# MicroController_USB_to_UART_Converter.net
KiCad netlist of a schematic drawn in Altium Designer
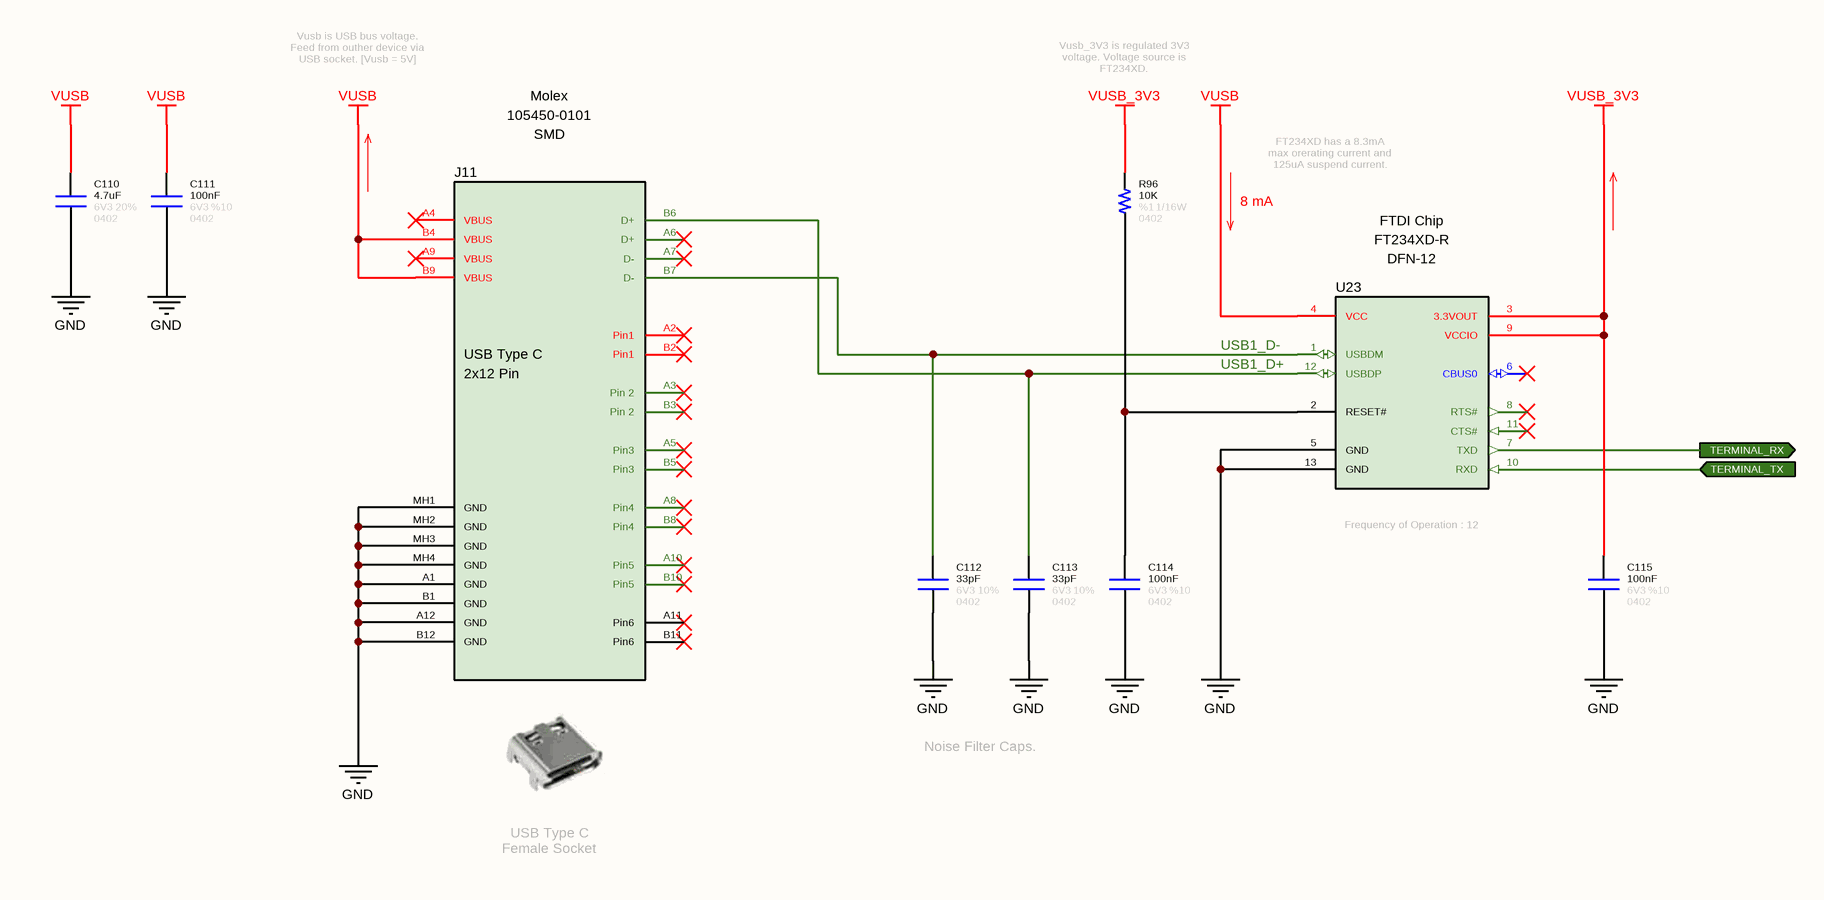
[diagram p0: MicroController USB to UART Converter.SchDoc]

(export (version "E")
  (design (tool "Eeschema 10.0.6"))
  (components
    (comp (ref "C110")
      (value "4.7uF")
      (footprint "CAPACITOR_0402")
      (description "Multilayer Ceramic Capacitors - SMD - 6V3 4.7uF X5R 0402 20%")
      (fields
        (field (name "MANUFACTURER PART NUMBER") "C0402C475M9PACTU")
        (field (name "TOLERANCE") "20%")
        (field (name "CASE") "0402")
        (field (name "VOLTAGE") "6V3")
        (field (name "Comment") "Capacitor - 4.7uF [0402] (Ceramic)")
      )
      (libsource (lib "Akkoyun") (part "Capacitor - 4.7uF [0402-6V3]"))
    )
    (comp (ref "C111")
      (value "100nF")
      (footprint "CAPACITOR_0402")
      (description "Capacitor - 100nF [0402-6V3] (Ceramic)")
      (fields
        (field (name "MANUFACTURER PART NUMBER") "04026D104KAT4A")
        (field (name "TOLERANCE") "%10")
        (field (name "VOLTAGE") "6V3")
        (field (name "CASE") "0402")
        (field (name "Comment") "Capacitor - 100nF [0402] (Ceramic)")
      )
      (libsource (lib "Akkoyun") (part "Capacitor - 100nF [0402-6V3]"))
    )
    (comp (ref "C112")
      (value "33pF")
      (footprint "CAPACITOR_0402")
      (description "Capacitor - 33pF [0402] (Ceramic)")
      (fields
        (field (name "MANUFACTURER PART NUMBER") "C0402C330J9RACAUTO")
        (field (name "TOLERANCE") "10%")
        (field (name "CASE") "0402")
        (field (name "VOLTAGE") "6V3")
      )
      (libsource (lib "Akkoyun") (part "Capacitor - 33pF [0402-6V3]"))
    )
    (comp (ref "C113")
      (value "33pF")
      (footprint "CAPACITOR_0402")
      (description "Capacitor - 33pF [0402] (Ceramic)")
      (fields
        (field (name "MANUFACTURER PART NUMBER") "C0402C330J9RACAUTO")
        (field (name "TOLERANCE") "10%")
        (field (name "CASE") "0402")
        (field (name "VOLTAGE") "6V3")
      )
      (libsource (lib "Akkoyun") (part "Capacitor - 33pF [0402-6V3]"))
    )
    (comp (ref "C114")
      (value "100nF")
      (footprint "CAPACITOR_0402")
      (description "Capacitor - 100nF [0402-6V3] (Ceramic)")
      (fields
        (field (name "MANUFACTURER PART NUMBER") "04026D104KAT4A")
        (field (name "TOLERANCE") "%10")
        (field (name "VOLTAGE") "6V3")
        (field (name "CASE") "0402")
        (field (name "Comment") "Capacitor - 100nF [0402] (Ceramic)")
      )
      (libsource (lib "Akkoyun") (part "Capacitor - 100nF [0402-6V3]"))
    )
    (comp (ref "C115")
      (value "100nF")
      (footprint "CAPACITOR_0402")
      (description "Capacitor - 100nF [0402-6V3] (Ceramic)")
      (fields
        (field (name "MANUFACTURER PART NUMBER") "04026D104KAT4A")
        (field (name "TOLERANCE") "%10")
        (field (name "VOLTAGE") "6V3")
        (field (name "CASE") "0402")
        (field (name "Comment") "Capacitor - 100nF [0402] (Ceramic)")
      )
      (libsource (lib "Akkoyun") (part "Capacitor - 100nF [0402-6V3]"))
    )
    (comp (ref "J11")
      (value "105450-0101")
      (footprint "USB Type C - Molex 105450-0101")
      (description "USB Shielded I/O Receptacle; Type C; Right Angle; Surface Mount; Gold over Nickel")
      (fields
        (field (name "MANUFACTURER NAME") "Molex")
        (field (name "MANUFACTURER PART NUMBER") "105450-0101")
        (field (name "CASE") "SMD")
      )
      (libsource (lib "Akkoyun") (part "Connector - USB Type C SMD Connector"))
    )
    (comp (ref "R96")
      (value "10K")
      (footprint "RESISTOR_0402")
      (description "Thick Film Resistors - SMD 1/16 W 10 KOhm 1%")
      (fields
        (field (name "MANUFACTURER PART NUMBER") "CRCW040210K0FKED")
        (field (name "TOLERANCE") "%1")
        (field (name "CASE") "0402")
        (field (name "POWER") "1/16W")
        (field (name "Comment") "10K - 0402 - %1 - 1/16W")
      )
      (libsource (lib "Akkoyun") (part "Resistor - 10K [0402]"))
    )
    (comp (ref "U23")
      (value "FT234XD-R")
      (footprint "FT234XD-R")
      (description "USB Interface IC USB to Serial UART Interface")
      (fields
        (field (name "MANUFACTURER NAME") "FTDI Chip")
        (field (name "MANUFACTURER PART NUMBER") "FT234XD-R")
        (field (name "CASE") "DFN-12")
      )
      (libsource (lib "Akkoyun") (part "IC - FT234XD-R"))
    )
  )
  (nets
    (net (code "1") (name "/TERMINAL_RX") (class "Default")
      (node (ref "U23") (pin "7") (pinfunction "TXD_7") (pintype "output"))
    )
    (net (code "2") (name "/TERMINAL_TX") (class "Default")
      (node (ref "U23") (pin "10") (pinfunction "RXD_10") (pintype "input"))
    )
    (net (code "3") (name "/USB1_D+") (class "Default")
      (node (ref "C113") (pin "2") (pinfunction "2_2") (pintype "passive"))
      (node (ref "J11") (pin "B6") (pinfunction "D+_B6") (pintype "passive"))
      (node (ref "U23") (pin "12") (pinfunction "USBDP_12") (pintype "bidirectional"))
    )
    (net (code "4") (name "/USB1_D-") (class "Default")
      (node (ref "C112") (pin "2") (pinfunction "2_2") (pintype "passive"))
      (node (ref "J11") (pin "B7") (pinfunction "D-_B7") (pintype "passive"))
      (node (ref "U23") (pin "1") (pinfunction "USBDM_1") (pintype "bidirectional"))
    )
    (net (code "5") (name "GND") (class "Default")
      (node (ref "C110") (pin "1") (pinfunction "1_1") (pintype "passive"))
      (node (ref "C111") (pin "1") (pinfunction "1_1") (pintype "passive"))
      (node (ref "C112") (pin "1") (pinfunction "1_1") (pintype "passive"))
      (node (ref "C113") (pin "1") (pinfunction "1_1") (pintype "passive"))
      (node (ref "C114") (pin "1") (pinfunction "1_1") (pintype "passive"))
      (node (ref "C115") (pin "1") (pinfunction "1_1") (pintype "passive"))
      (node (ref "J11") (pin "A1") (pinfunction "GND_A1") (pintype "passive"))
      (node (ref "J11") (pin "A12") (pinfunction "GND_A12") (pintype "passive"))
      (node (ref "J11") (pin "B1") (pinfunction "GND_B1") (pintype "passive"))
      (node (ref "J11") (pin "B12") (pinfunction "GND_B12") (pintype "passive"))
      (node (ref "J11") (pin "MH1") (pinfunction "GND_MH1") (pintype "passive"))
      (node (ref "J11") (pin "MH2") (pinfunction "GND_MH2") (pintype "passive"))
      (node (ref "J11") (pin "MH3") (pinfunction "GND_MH3") (pintype "passive"))
      (node (ref "J11") (pin "MH4") (pinfunction "GND_MH4") (pintype "passive"))
      (node (ref "U23") (pin "13") (pinfunction "GND_13") (pintype "power_in"))
      (node (ref "U23") (pin "5") (pinfunction "GND_5") (pintype "power_in"))
    )
    (net (code "6") (name "Net-(U23-RESET#)") (class "Default")
      (node (ref "C114") (pin "2") (pinfunction "2_2") (pintype "passive"))
      (node (ref "R96") (pin "1") (pinfunction "1_1") (pintype "passive"))
      (node (ref "U23") (pin "2") (pinfunction "RESET#_2") (pintype "passive"))
    )
    (net (code "7") (name "VUSB") (class "Default")
      (node (ref "C110") (pin "2") (pinfunction "2_2") (pintype "passive"))
      (node (ref "C111") (pin "2") (pinfunction "2_2") (pintype "passive"))
      (node (ref "J11") (pin "B4") (pinfunction "VBUS_B4") (pintype "passive"))
      (node (ref "J11") (pin "B9") (pinfunction "VBUS_B9") (pintype "passive"))
      (node (ref "U23") (pin "4") (pinfunction "VCC_4") (pintype "power_in"))
    )
    (net (code "8") (name "VUSB_3V3") (class "Default")
      (node (ref "C115") (pin "2") (pinfunction "2_2") (pintype "passive"))
      (node (ref "R96") (pin "2") (pinfunction "2_2") (pintype "passive"))
      (node (ref "U23") (pin "3") (pinfunction "3.3VOUT_3") (pintype "power_in"))
      (node (ref "U23") (pin "9") (pinfunction "VCCIO_9") (pintype "power_in"))
    )
    (net (code "9") (name "unconnected-(J11-D+-PadA6)") (class "Default")
      (node (ref "J11") (pin "A6") (pinfunction "D+_A6") (pintype "passive+no_connect"))
    )
    (net (code "10") (name "unconnected-(J11-D--PadA7)") (class "Default")
      (node (ref "J11") (pin "A7") (pinfunction "D-_A7") (pintype "passive+no_connect"))
    )
    (net (code "11") (name "unconnected-(J11-Pin1-PadA2)") (class "Default")
      (node (ref "J11") (pin "A2") (pinfunction "Pin1_A2") (pintype "passive+no_connect"))
    )
    (net (code "12") (name "unconnected-(J11-Pin1-PadB2)") (class "Default")
      (node (ref "J11") (pin "B2") (pinfunction "Pin1_B2") (pintype "passive+no_connect"))
    )
    (net (code "13") (name "unconnected-(J11-Pin3-PadA5)") (class "Default")
      (node (ref "J11") (pin "A5") (pinfunction "Pin3_A5") (pintype "passive+no_connect"))
    )
    (net (code "14") (name "unconnected-(J11-Pin3-PadB5)") (class "Default")
      (node (ref "J11") (pin "B5") (pinfunction "Pin3_B5") (pintype "passive+no_connect"))
    )
    (net (code "15") (name "unconnected-(J11-Pin4-PadA8)") (class "Default")
      (node (ref "J11") (pin "A8") (pinfunction "Pin4_A8") (pintype "passive+no_connect"))
    )
    (net (code "16") (name "unconnected-(J11-Pin4-PadB8)") (class "Default")
      (node (ref "J11") (pin "B8") (pinfunction "Pin4_B8") (pintype "passive+no_connect"))
    )
    (net (code "17") (name "unconnected-(J11-Pin5-PadA10)") (class "Default")
      (node (ref "J11") (pin "A10") (pinfunction "Pin5_A10") (pintype "passive+no_connect"))
    )
    (net (code "18") (name "unconnected-(J11-Pin5-PadB10)") (class "Default")
      (node (ref "J11") (pin "B10") (pinfunction "Pin5_B10") (pintype "passive+no_connect"))
    )
    (net (code "19") (name "unconnected-(J11-Pin6-PadA11)") (class "Default")
      (node (ref "J11") (pin "A11") (pinfunction "Pin6_A11") (pintype "passive+no_connect"))
    )
    (net (code "20") (name "unconnected-(J11-Pin6-PadB11)") (class "Default")
      (node (ref "J11") (pin "B11") (pinfunction "Pin6_B11") (pintype "passive+no_connect"))
    )
    (net (code "21") (name "unconnected-(J11-Pin_2-PadA3)") (class "Default")
      (node (ref "J11") (pin "A3") (pinfunction "Pin_2_A3") (pintype "passive+no_connect"))
    )
    (net (code "22") (name "unconnected-(J11-Pin_2-PadB3)") (class "Default")
      (node (ref "J11") (pin "B3") (pinfunction "Pin_2_B3") (pintype "passive+no_connect"))
    )
    (net (code "23") (name "unconnected-(J11-VBUS-PadA4)") (class "Default")
      (node (ref "J11") (pin "A4") (pinfunction "VBUS_A4") (pintype "passive+no_connect"))
    )
    (net (code "24") (name "unconnected-(J11-VBUS-PadA9)") (class "Default")
      (node (ref "J11") (pin "A9") (pinfunction "VBUS_A9") (pintype "passive+no_connect"))
    )
    (net (code "25") (name "unconnected-(U23-CBUS0-Pad6)") (class "Default")
      (node (ref "U23") (pin "6") (pinfunction "CBUS0_6") (pintype "bidirectional+no_connect"))
    )
    (net (code "26") (name "unconnected-(U23-CTS#-Pad11)") (class "Default")
      (node (ref "U23") (pin "11") (pinfunction "CTS#_11") (pintype "input+no_connect"))
    )
    (net (code "27") (name "unconnected-(U23-RTS#-Pad8)") (class "Default")
      (node (ref "U23") (pin "8") (pinfunction "RTS#_8") (pintype "output+no_connect"))
    )
  )
)
